# LPCB218_-_MLP_CHANNEL.net
KiCad netlist of a schematic drawn in Altium Designer
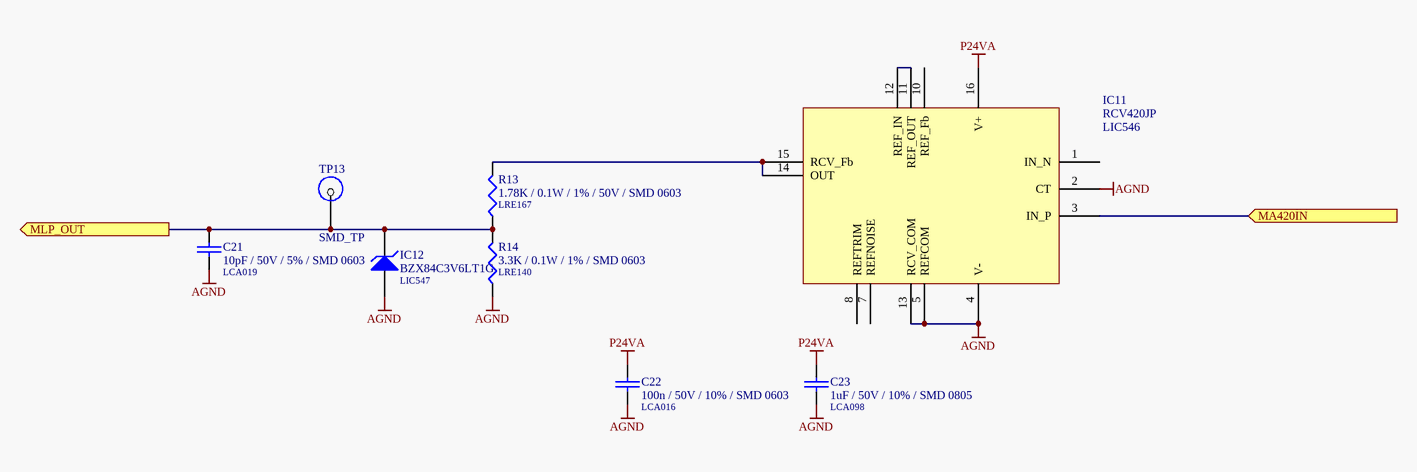
[diagram p0: LPCB218 - MLP CHANNEL.SchDoc]

(export (version "E")
  (design (tool "Eeschema 10.0.6"))
  (components
    (comp (ref "C21")
      (value "10pF / 50V / 5% / SMD 0603")
      (footprint "LFP011__CC1608-0603-IPC7351_B")
      (description "Capacitor, Ceramic Chip, 10pF, 50V, 5%, SMD 0603 [LCA019]")
      (fields (field (name "LDL_NUMBER") "LCA019"))
      (libsource (lib "LDL_Capacitors") (part "10pF / 50V / 5% / SMD 0603"))
    )
    (comp (ref "C22")
      (value "100n / 50V / 10% / SMD 0603")
      (footprint "LFP011__CC1608-0603-IPC7351_B")
      (description "Capacitor, Ceramic Chip, 100nF (0.1uF), 50V, 5%, SMD 0603 [LCA016]")
      (fields (field (name "LDL_NUMBER") "LCA016"))
      (libsource (lib "LDL_Capacitors") (part "100n / 50V / 10% / SMD 0603"))
    )
    (comp (ref "C23")
      (value "1uF / 50V / 10% / SMD 0805")
      (footprint "LFP010__CC2012-0805-IPC7351_B")
      (description "Capacitor, Ceramic Chip, 1uF, 50V, SMD 0805 [LCA098]")
      (fields (field (name "LDL_NUMBER") "LCA098"))
      (libsource (lib "LDL_Capacitors") (part "1uF / 50V / 10% / SMD 0805"))
    )
    (comp (ref "IC11")
      (value "RCV420JP")
      (footprint "DIP-P16/X1.5")
      (description "IC, 4-20mA Interface, DIP16 [LIC546]")
      (fields (field (name "LDL_NUMBER") "LIC546"))
      (libsource (lib "LDL_Semiconductors") (part "RCV420JP"))
    )
    (comp (ref "IC12")
      (value "BZX84C3V6LT1G")
      (footprint "LFP021__SOT23")
      (description "Diode, Zener, 3.6V, 0.225W, SMD [LIC083]")
      (fields (field (name "LDL_NUMBER") "LIC547"))
      (libsource (lib "LDL_Semiconductors") (part "BZX84C3V6LT1G"))
    )
    (comp (ref "R13")
      (value "1.78K / 0.1W / 1% / 50V / SMD 0603")
      (footprint "LFP020__CR1608-0603-IPC7351_B")
      (description "Resistor, Ceramic Chip, 1.78K, 0.1W, 1%, SMD 0603 [LRE167]")
      (fields (field (name "LDL_NUMBER") "LRE167"))
      (libsource (lib "LDL_Resistors") (part "1.78K / 0.1W / 1% / 50V / SMD 0603"))
    )
    (comp (ref "R14")
      (value "3.3K / 0.1W / 1% / SMD 0603")
      (footprint "LFP020__CR1608-0603-IPC7351_B")
      (description "Resistor, Ceramic Chip, 3.3K0, 0.1W, 1%, SMD 0603 [LRE140]")
      (fields (field (name "LDL_NUMBER") "LRE140"))
      (libsource (lib "LDL_Resistors") (part "3.3K / 0.1W / 1% / SMD 0603"))
    )
    (comp (ref "TP13")
      (value "SMD_TP")
      (footprint "SMD-TP")
      (description "SMD Test Point")
      (libsource (lib "LDL_Connectors") (part "SMD_TP"))
    )
  )
  (nets
    (net (code "1") (name "/MA420IN") (class "Default")
      (node (ref "IC11") (pin "3") (pinfunction "IN_P_3") (pintype "passive"))
    )
    (net (code "2") (name "/MLP_OUT") (class "Default")
      (node (ref "C21") (pin "1") (pintype "passive"))
      (node (ref "IC12") (pin "3") (pinfunction "K_3") (pintype "passive"))
      (node (ref "R13") (pin "1") (pintype "passive"))
      (node (ref "R14") (pin "2") (pintype "passive"))
      (node (ref "TP13") (pin "1") (pintype "passive"))
    )
    (net (code "3") (name "AGND") (class "Default")
      (node (ref "C21") (pin "2") (pintype "passive"))
      (node (ref "C22") (pin "2") (pintype "passive"))
      (node (ref "C23") (pin "2") (pintype "passive"))
      (node (ref "IC11") (pin "13") (pinfunction "RCV_COM_13") (pintype "passive"))
      (node (ref "IC11") (pin "2") (pinfunction "CT_2") (pintype "passive"))
      (node (ref "IC11") (pin "4") (pinfunction "V-_4") (pintype "power_in"))
      (node (ref "IC11") (pin "5") (pinfunction "REFCOM_5") (pintype "passive"))
      (node (ref "IC12") (pin "1") (pinfunction "A_1") (pintype "passive"))
      (node (ref "R14") (pin "1") (pintype "passive"))
    )
    (net (code "4") (name "Net-(IC11-OUT)") (class "Default")
      (node (ref "IC11") (pin "14") (pinfunction "OUT_14") (pintype "passive"))
      (node (ref "IC11") (pin "15") (pinfunction "RCV_Fb_15") (pintype "passive"))
      (node (ref "R13") (pin "2") (pintype "passive"))
    )
    (net (code "5") (name "Net-(IC11-REF_IN)") (class "Default")
      (node (ref "IC11") (pin "11") (pinfunction "REF_OUT_11") (pintype "passive"))
      (node (ref "IC11") (pin "12") (pinfunction "REF_IN_12") (pintype "passive"))
    )
    (net (code "6") (name "P24VA") (class "Default")
      (node (ref "C22") (pin "1") (pintype "passive"))
      (node (ref "C23") (pin "1") (pintype "passive"))
      (node (ref "IC11") (pin "16") (pinfunction "V+_16") (pintype "power_in"))
    )
    (net (code "7") (name "unconnected-(IC11-IN_N-Pad1)") (class "Default")
      (node (ref "IC11") (pin "1") (pinfunction "IN_N_1") (pintype "passive"))
    )
    (net (code "8") (name "unconnected-(IC11-REFNOISE-Pad7)") (class "Default")
      (node (ref "IC11") (pin "7") (pinfunction "REFNOISE_7") (pintype "passive"))
    )
    (net (code "9") (name "unconnected-(IC11-REFTRIM-Pad8)") (class "Default")
      (node (ref "IC11") (pin "8") (pinfunction "REFTRIM_8") (pintype "passive"))
    )
    (net (code "10") (name "unconnected-(IC11-REF_Fb-Pad10)") (class "Default")
      (node (ref "IC11") (pin "10") (pinfunction "REF_Fb_10") (pintype "passive"))
    )
  )
)
